# USBSticker01-02.net
KiCad netlist of a schematic drawn in Altium Designer
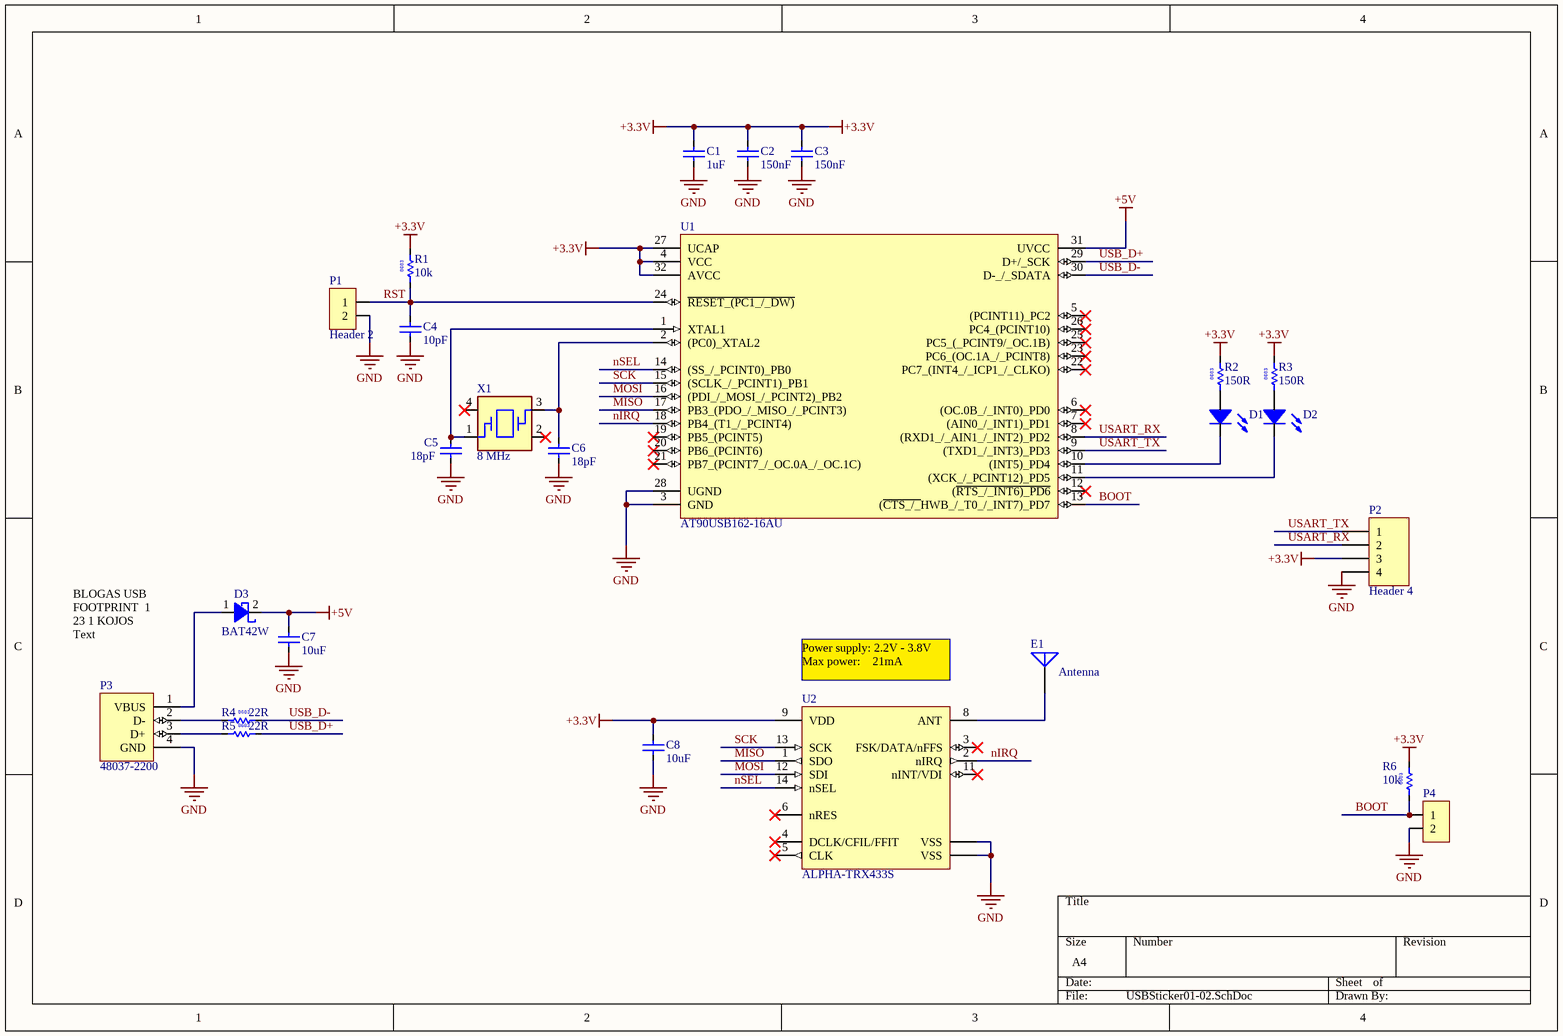
[diagram p0: USBSticker01-02.SchDoc]

(export (version "E")
  (design (tool "Eeschema 10.0.6"))
  (components
    (comp (ref "C1")
      (value "1uF")
      (footprint "CAPC1608N")
      (description "MLCC, 0603, X6S, 25V, 1uF")
      (fields (field (name "PART NUMBER") "C0000022") (field (name "VOLTAGE") "25"))
      (libsource (lib "KTU_DB") (part "C_SM"))
    )
    (comp (ref "C2")
      (value "150nF")
      (footprint "CAPC1608N")
      (description "MLCC, 150nF 16V -20+80% Y5V")
      (fields (field (name "PART NUMBER") "C0000001") (field (name "VOLTAGE") "16"))
      (libsource (lib "KTU_DB") (part "C_SM"))
    )
    (comp (ref "C3")
      (value "150nF")
      (footprint "CAPC1608N")
      (description "MLCC, 150nF 16V -20+80% Y5V")
      (fields (field (name "PART NUMBER") "C0000001") (field (name "VOLTAGE") "16"))
      (libsource (lib "KTU_DB") (part "C_SM"))
    )
    (comp (ref "C4")
      (value "10pF")
      (footprint "CAPC1608N")
      (description "MLCC, 0603, NP0, 50V, 10PF")
      (fields (field (name "PART NUMBER") "C0000042") (field (name "VOLTAGE") "100"))
      (libsource (lib "KTU_DB") (part "C_SM"))
    )
    (comp (ref "C5")
      (value "18pF")
      (footprint "CAPC2012N")
      (description "MLCC, 0805, NPO, 50V, 18pF")
      (fields (field (name "PART NUMBER") "C0000048") (field (name "VOLTAGE") "50"))
      (libsource (lib "KTU_DB") (part "C_SM"))
    )
    (comp (ref "C6")
      (value "18pF")
      (footprint "CAPC2012N")
      (description "MLCC, 0805, NPO, 50V, 18pF")
      (fields (field (name "PART NUMBER") "C0000048") (field (name "VOLTAGE") "50"))
      (libsource (lib "KTU_DB") (part "C_SM"))
    )
    (comp (ref "C7")
      (value "10uF")
      (footprint "CAPC3216N")
      (description "MLCC, 10uF 25V -20%, +80% Y5V 1206")
      (fields (field (name "PART NUMBER") "C0000011") (field (name "VOLTAGE") "25"))
      (libsource (lib "KTU_DB") (part "C_SM"))
    )
    (comp (ref "C8")
      (value "10uF")
      (footprint "CAPC3216N")
      (description "MLCC, 10uF 25V -20%, +80% Y5V 1206")
      (fields (field (name "PART NUMBER") "C0000011") (field (name "VOLTAGE") "25"))
      (libsource (lib "KTU_DB") (part "C_SM"))
    )
    (comp (ref "D1")
      (value "KPT-2012QBC-D")
      (footprint "D0805")
      (description "LED, SMD, 0805, BLUE, 100mCd")
      (fields (field (name "PART NUMBER") "D0000005") (field (name "MANUFACTURER") "KINGBRIGHT"))
      (libsource (lib "KTU_DB") (part "LED"))
    )
    (comp (ref "D2")
      (value "KPT-2012QBC-D")
      (footprint "D0805")
      (description "LED, SMD, 0805, BLUE, 100mCd")
      (fields (field (name "PART NUMBER") "D0000005") (field (name "MANUFACTURER") "KINGBRIGHT"))
      (libsource (lib "KTU_DB") (part "LED"))
    )
    (comp (ref "D3")
      (value "BAT42W")
      (footprint "SOD123")
      (description "Diode Schottkey, 30V, Vf=1V, If=1A, rrt=5ns, SOD123, -55°C to +125°C")
      (fields (field (name "PART NUMBER") "D0000003") (field (name "MANUFACTURER") "VISHAY SEMICONDUCTOR"))
      (libsource (lib "KTU_DB") (part "Diode_SCHOTTKY"))
    )
    (comp (ref "E1")
      (value "Antenna")
      (description "Generic Antenna")
      (fields (field (name "PUBLISHER") "Altium Limited"))
      (libsource (lib "Miscellaneous Devices") (part "Antenna"))
    )
    (comp (ref "P1")
      (value "Header 2")
      (footprint "HDR1X2")
      (description "Header, 2-Pin")
      (fields (field (name "PUBLISHER") "Altium Limited"))
      (libsource (lib "UserSchlib") (part "Header 2"))
    )
    (comp (ref "P2")
      (value "Header 4")
      (footprint "HDR1X4")
      (description "Header, 4-Pin")
      (fields (field (name "PUBLISHER") "Altium Limited"))
      (libsource (lib "Miscellaneous Connectors") (part "Header 4"))
    )
    (comp (ref "P3")
      (value "48037-2200")
      (footprint "MOLEX 48037-2200")
      (description "SOCKET, USB, PCB, R/A, TYPE A")
      (fields (field (name "MANUFACTURER") "MOLEX"))
      (libsource (lib "UserSchlib") (part "48037-2200"))
    )
    (comp (ref "P4")
      (value "Header 2")
      (footprint "HDR1X2")
      (description "Header, 2-Pin")
      (fields (field (name "PUBLISHER") "Altium Limited"))
      (libsource (lib "") (part "Header 2_1"))
    )
    (comp (ref "R1")
      (value "10k")
      (footprint "RESC1608N")
      (description "Res, 10K 0.063W 75V 1%  0603")
      (fields (field (name "TOLERANCE") "±1%") (field (name "POWER") "0.063W"))
      (libsource (lib "KTU_DB") (part "R0603"))
    )
    (comp (ref "R2")
      (value "150R")
      (footprint "RESC1608N")
      (description "150R 5% 0603 1/10W")
      (fields (field (name "TOLERANCE") "±5%") (field (name "POWER") "1/10W"))
      (libsource (lib "KTU_DB") (part "R0603"))
    )
    (comp (ref "R3")
      (value "150R")
      (footprint "RESC1608N")
      (description "150R 5% 0603 1/10W")
      (fields (field (name "TOLERANCE") "±5%") (field (name "POWER") "1/10W"))
      (libsource (lib "KTU_DB") (part "R0603"))
    )
    (comp (ref "R4")
      (value "22R")
      (footprint "RESC1608X50N")
      (description "Res, 22R, 0603 (1608 metric), ±1%, 100mW, 75V")
      (libsource (lib "KTU_DB") (part "R0603"))
    )
    (comp (ref "R5")
      (value "22R")
      (footprint "RESC1608X50N")
      (description "Res, 22R, 0603 (1608 metric), ±1%, 100mW, 75V")
      (libsource (lib "KTU_DB") (part "R0603"))
    )
    (comp (ref "R6")
      (value "10k")
      (footprint "RESC1608N")
      (description "Res, 10K 0.063W 75V 1%  0603")
      (fields (field (name "TOLERANCE") "±1%") (field (name "POWER") "0.063W"))
      (libsource (lib "KTU_DB") (part "R0603"))
    )
    (comp (ref "U1")
      (value "AT90USB162-16AU")
      (footprint "QFP80P900X900X120-32N")
      (fields (field (name "MANUFACTURER") "Atmel"))
      (libsource (lib "UserSchlib") (part "AT90USB162-16AU"))
    )
    (comp (ref "U2")
      (value "ALPHA-TRX433S")
      (footprint "ALPHA-TRX")
      (description "RF SOLUTIONS  ALPHA-TRX433S  RF MODULE, TRANSCEIVER, FSK, 433MHZ")
      (fields (field (name "MANUFACTURER") "RF SOLUTIONS"))
      (libsource (lib "UserSchlib") (part "ALPHA-TRX433S"))
    )
    (comp (ref "X1")
      (value "8 MHz")
      (footprint "2SMX-3SMXB")
      (description "CRYSTAL, 8M, 18PF CL, 6X3.6MM SMT")
      (fields (field (name "PART NUMBER") "M0000014") (field (name "TOLERANCE") "± 20ppm"))
      (libsource (lib "KTU_DB") (part "XTAL2"))
    )
  )
  (nets
    (net (code "1") (name "+3.3V") (class "Default")
      (node (ref "C1") (pin "2") (pinfunction "2_2") (pintype "passive"))
      (node (ref "C2") (pin "2") (pinfunction "2_2") (pintype "passive"))
      (node (ref "C3") (pin "2") (pinfunction "2_2") (pintype "passive"))
      (node (ref "C8") (pin "2") (pinfunction "2_2") (pintype "passive"))
      (node (ref "P2") (pin "3") (pinfunction "3_3") (pintype "passive"))
      (node (ref "R1") (pin "2") (pinfunction "2_2") (pintype "passive"))
      (node (ref "R2") (pin "2") (pinfunction "2_2") (pintype "passive"))
      (node (ref "R3") (pin "2") (pinfunction "2_2") (pintype "passive"))
      (node (ref "R6") (pin "2") (pinfunction "2_2") (pintype "passive"))
      (node (ref "U1") (pin "27") (pinfunction "UCAP_27") (pintype "power_in"))
      (node (ref "U1") (pin "32") (pinfunction "AVCC_32") (pintype "power_in"))
      (node (ref "U1") (pin "4") (pinfunction "VCC_4") (pintype "power_in"))
      (node (ref "U2") (pin "9") (pinfunction "VDD_9") (pintype "power_in"))
    )
    (net (code "2") (name "+5V") (class "Default")
      (node (ref "C7") (pin "2") (pinfunction "2_2") (pintype "passive"))
      (node (ref "D3") (pin "2") (pinfunction "CATHODE_2") (pintype "passive"))
      (node (ref "U1") (pin "31") (pinfunction "UVCC_31") (pintype "power_in"))
    )
    (net (code "3") (name "/BOOT") (class "Default")
      (node (ref "P4") (pin "1") (pinfunction "1_1") (pintype "passive"))
      (node (ref "R6") (pin "1") (pinfunction "1_1") (pintype "passive"))
      (node (ref "U1") (pin "13") (pinfunction "(~{CTS_/_}HWB_/_T0_/_INT7)_PD7_13") (pintype "bidirectional"))
    )
    (net (code "4") (name "/MISO") (class "Default")
      (node (ref "U1") (pin "17") (pinfunction "PB3_(PDO_/_MISO_/_PCINT3)_17") (pintype "bidirectional"))
      (node (ref "U2") (pin "1") (pinfunction "SDO_1") (pintype "output"))
    )
    (net (code "5") (name "/MOSI") (class "Default")
      (node (ref "U1") (pin "16") (pinfunction "(PDI_/_MOSI_/_PCINT2)_PB2_16") (pintype "bidirectional"))
      (node (ref "U2") (pin "12") (pinfunction "SDI_12") (pintype "input"))
    )
    (net (code "6") (name "/RST") (class "Default")
      (node (ref "C4") (pin "2") (pinfunction "2_2") (pintype "passive"))
      (node (ref "P1") (pin "1") (pinfunction "1_1") (pintype "passive"))
      (node (ref "R1") (pin "1") (pinfunction "1_1") (pintype "passive"))
      (node (ref "U1") (pin "24") (pinfunction "~{RESET_(PC1_/_DW)}_24") (pintype "bidirectional"))
    )
    (net (code "7") (name "/SCK") (class "Default")
      (node (ref "U1") (pin "15") (pinfunction "(SCLK_/_PCINT1)_PB1_15") (pintype "bidirectional"))
      (node (ref "U2") (pin "13") (pinfunction "SCK_13") (pintype "input"))
    )
    (net (code "8") (name "/USART_RX") (class "Default")
      (node (ref "P2") (pin "2") (pinfunction "2_2") (pintype "passive"))
      (node (ref "U1") (pin "8") (pinfunction "(RXD1_/_AIN1_/_INT2)_PD2_8") (pintype "bidirectional"))
    )
    (net (code "9") (name "/USART_TX") (class "Default")
      (node (ref "P2") (pin "1") (pinfunction "1_1") (pintype "passive"))
      (node (ref "U1") (pin "9") (pinfunction "(TXD1_/_INT3)_PD3_9") (pintype "bidirectional"))
    )
    (net (code "10") (name "/USB_D+") (class "Default")
      (node (ref "R5") (pin "2") (pinfunction "2_2") (pintype "passive"))
      (node (ref "U1") (pin "29") (pinfunction "D+/_SCK_29") (pintype "bidirectional"))
    )
    (net (code "11") (name "/USB_D-") (class "Default")
      (node (ref "R4") (pin "2") (pinfunction "2_2") (pintype "passive"))
      (node (ref "U1") (pin "30") (pinfunction "D-_/_SDATA_30") (pintype "bidirectional"))
    )
    (net (code "12") (name "/nIRQ") (class "Default")
      (node (ref "U1") (pin "18") (pinfunction "PB4_(T1_/_PCINT4)_18") (pintype "bidirectional"))
      (node (ref "U2") (pin "2") (pinfunction "nIRQ_2") (pintype "output"))
    )
    (net (code "13") (name "/nSEL") (class "Default")
      (node (ref "U1") (pin "14") (pinfunction "(SS_/_PCINT0)_PB0_14") (pintype "bidirectional"))
      (node (ref "U2") (pin "14") (pinfunction "nSEL_14") (pintype "input"))
    )
    (net (code "14") (name "GND") (class "Default")
      (node (ref "C1") (pin "1") (pinfunction "1_1") (pintype "passive"))
      (node (ref "C2") (pin "1") (pinfunction "1_1") (pintype "passive"))
      (node (ref "C3") (pin "1") (pinfunction "1_1") (pintype "passive"))
      (node (ref "C4") (pin "1") (pinfunction "1_1") (pintype "passive"))
      (node (ref "C5") (pin "1") (pinfunction "1_1") (pintype "passive"))
      (node (ref "C6") (pin "1") (pinfunction "1_1") (pintype "passive"))
      (node (ref "C7") (pin "1") (pinfunction "1_1") (pintype "passive"))
      (node (ref "C8") (pin "1") (pinfunction "1_1") (pintype "passive"))
      (node (ref "P1") (pin "2") (pinfunction "2_2") (pintype "passive"))
      (node (ref "P2") (pin "4") (pinfunction "4_4") (pintype "passive"))
      (node (ref "P3") (pin "4") (pinfunction "GND_4") (pintype "power_in"))
      (node (ref "P4") (pin "2") (pinfunction "2_2") (pintype "passive"))
      (node (ref "U1") (pin "28") (pinfunction "UGND_28") (pintype "passive"))
      (node (ref "U1") (pin "3") (pinfunction "GND_3") (pintype "passive"))
      (node (ref "U2") (pin "10") (pinfunction "VSS_10") (pintype "power_in"))
      (node (ref "U2") (pin "7") (pinfunction "VSS_7") (pintype "power_in"))
    )
    (net (code "15") (name "Net-(D1-Pad1)") (class "Default")
      (node (ref "D1") (pin "1") (pinfunction "1_1") (pintype "passive"))
      (node (ref "R2") (pin "1") (pinfunction "1_1") (pintype "passive"))
    )
    (net (code "16") (name "Net-(D2-Pad1)") (class "Default")
      (node (ref "D2") (pin "1") (pinfunction "1_1") (pintype "passive"))
      (node (ref "R3") (pin "1") (pinfunction "1_1") (pintype "passive"))
    )
    (net (code "17") (name "Net-(D3-ANODE)") (class "Default")
      (node (ref "D3") (pin "1") (pinfunction "ANODE_1") (pintype "passive"))
      (node (ref "P3") (pin "1") (pinfunction "VBUS_1") (pintype "power_in"))
    )
    (net (code "18") (name "Net-(E1-A)") (class "Default")
      (node (ref "E1") (pin "1") (pinfunction "A_1") (pintype "passive"))
      (node (ref "U2") (pin "8") (pinfunction "ANT_8") (pintype "passive"))
    )
    (net (code "19") (name "Net-(P3-D+)") (class "Default")
      (node (ref "P3") (pin "3") (pinfunction "D+_3") (pintype "bidirectional"))
      (node (ref "R5") (pin "1") (pinfunction "1_1") (pintype "passive"))
    )
    (net (code "20") (name "Net-(P3-D-)") (class "Default")
      (node (ref "P3") (pin "2") (pinfunction "D-_2") (pintype "bidirectional"))
      (node (ref "R4") (pin "1") (pinfunction "1_1") (pintype "passive"))
    )
    (net (code "21") (name "Net-(U1-(INT5)_PD4)") (class "Default")
      (node (ref "D1") (pin "2") (pinfunction "2_2") (pintype "passive"))
      (node (ref "U1") (pin "10") (pinfunction "(INT5)_PD4_10") (pintype "bidirectional"))
    )
    (net (code "22") (name "Net-(U1-(PC0)_XTAL2)") (class "Default")
      (node (ref "C6") (pin "2") (pinfunction "2_2") (pintype "passive"))
      (node (ref "U1") (pin "2") (pinfunction "(PC0)_XTAL2_2") (pintype "bidirectional"))
      (node (ref "X1") (pin "3") (pinfunction "3_3") (pintype "passive"))
    )
    (net (code "23") (name "Net-(U1-(XCK_{slash}_PCINT12)_PD5)") (class "Default")
      (node (ref "D2") (pin "2") (pinfunction "2_2") (pintype "passive"))
      (node (ref "U1") (pin "11") (pinfunction "(XCK_/_PCINT12)_PD5_11") (pintype "bidirectional"))
    )
    (net (code "24") (name "Net-(U1-XTAL1)") (class "Default")
      (node (ref "C5") (pin "2") (pinfunction "2_2") (pintype "passive"))
      (node (ref "U1") (pin "1") (pinfunction "XTAL1_1") (pintype "input"))
      (node (ref "X1") (pin "1") (pinfunction "1_1") (pintype "passive"))
    )
    (net (code "25") (name "unconnected-(U1-(AIN0_{slash}_INT1)_PD1-Pad7)") (class "Default")
      (node (ref "U1") (pin "7") (pinfunction "(AIN0_/_INT1)_PD1_7") (pintype "bidirectional+no_connect"))
    )
    (net (code "26") (name "unconnected-(U1-(OC.0B_{slash}_INT0)_PD0-Pad6)") (class "Default")
      (node (ref "U1") (pin "6") (pinfunction "(OC.0B_/_INT0)_PD0_6") (pintype "bidirectional+no_connect"))
    )
    (net (code "27") (name "unconnected-(U1-(PCINT11)_PC2-Pad5)") (class "Default")
      (node (ref "U1") (pin "5") (pinfunction "(PCINT11)_PC2_5") (pintype "bidirectional+no_connect"))
    )
    (net (code "28") (name "unconnected-(U1-(~{RTS_{slash}_INT6)_PD6}-Pad12)") (class "Default")
      (node (ref "U1") (pin "12") (pinfunction "(~{RTS_/_INT6)_PD6}_12") (pintype "bidirectional+no_connect"))
    )
    (net (code "29") (name "unconnected-(U1-PB5_(PCINT5)-Pad19)") (class "Default")
      (node (ref "U1") (pin "19") (pinfunction "PB5_(PCINT5)_19") (pintype "bidirectional+no_connect"))
    )
    (net (code "30") (name "unconnected-(U1-PB6_(PCINT6)-Pad20)") (class "Default")
      (node (ref "U1") (pin "20") (pinfunction "PB6_(PCINT6)_20") (pintype "bidirectional+no_connect"))
    )
    (net (code "31") (name "unconnected-(U1-PB7_(PCINT7_{slash}_OC.0A_{slash}_OC.1C)-Pad21)") (class "Default")
      (node (ref "U1") (pin "21") (pinfunction "PB7_(PCINT7_/_OC.0A_/_OC.1C)_21") (pintype "bidirectional+no_connect"))
    )
    (net (code "32") (name "unconnected-(U1-PC4_(PCINT10)-Pad26)") (class "Default")
      (node (ref "U1") (pin "26") (pinfunction "PC4_(PCINT10)_26") (pintype "bidirectional+no_connect"))
    )
    (net (code "33") (name "unconnected-(U1-PC5_(_PCINT9{slash}_OC.1B)-Pad25)") (class "Default")
      (node (ref "U1") (pin "25") (pinfunction "PC5_(_PCINT9/_OC.1B)_25") (pintype "bidirectional+no_connect"))
    )
    (net (code "34") (name "unconnected-(U1-PC6_(OC.1A_{slash}_PCINT8)-Pad23)") (class "Default")
      (node (ref "U1") (pin "23") (pinfunction "PC6_(OC.1A_/_PCINT8)_23") (pintype "bidirectional+no_connect"))
    )
    (net (code "35") (name "unconnected-(U1-PC7_(INT4_{slash}_ICP1_{slash}_CLKO)-Pad22)") (class "Default")
      (node (ref "U1") (pin "22") (pinfunction "PC7_(INT4_/_ICP1_/_CLKO)_22") (pintype "bidirectional+no_connect"))
    )
    (net (code "36") (name "unconnected-(U2-CLK-Pad5)") (class "Default")
      (node (ref "U2") (pin "5") (pinfunction "CLK_5") (pintype "output+no_connect"))
    )
    (net (code "37") (name "unconnected-(U2-DCLK{slash}CFIL{slash}FFIT-Pad4)") (class "Default")
      (node (ref "U2") (pin "4") (pinfunction "DCLK/CFIL/FFIT_4") (pintype "passive+no_connect"))
    )
    (net (code "38") (name "unconnected-(U2-FSK{slash}DATA{slash}nFFS-Pad3)") (class "Default")
      (node (ref "U2") (pin "3") (pinfunction "FSK/DATA/nFFS_3") (pintype "bidirectional+no_connect"))
    )
    (net (code "39") (name "unconnected-(U2-nINT{slash}VDI-Pad11)") (class "Default")
      (node (ref "U2") (pin "11") (pinfunction "nINT/VDI_11") (pintype "bidirectional+no_connect"))
    )
    (net (code "40") (name "unconnected-(U2-nRES-Pad6)") (class "Default")
      (node (ref "U2") (pin "6") (pinfunction "nRES_6") (pintype "passive+no_connect"))
    )
    (net (code "41") (name "unconnected-(X1-Pad2)") (class "Default")
      (node (ref "X1") (pin "2") (pinfunction "2_2") (pintype "passive+no_connect"))
    )
    (net (code "42") (name "unconnected-(X1-Pad4)") (class "Default")
      (node (ref "X1") (pin "4") (pinfunction "4_4") (pintype "passive+no_connect"))
    )
  )
)
